# BoardA-Storage.net
KiCad netlist of a schematic drawn in Altium Designer
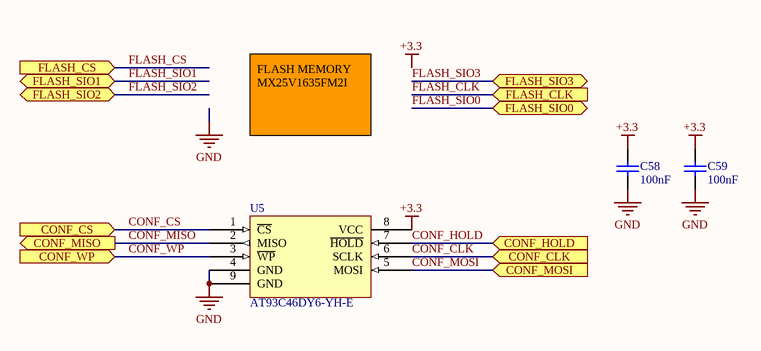
[diagram p0: BoardA-Storage.SchDoc]

(export (version "E")
  (design (tool "Eeschema 10.0.6"))
  (components
    (comp (ref "C58")
      (value "100nF")
      (footprint "CAPC0603X33X15ML03T05")
      (fields (field (name "MANUFACTURER") "Samsung") (field (name "PART NUMBER") "CL03A104KQ3NNNC"))
      (libsource (lib "Altium Content Vault") (part "CAP"))
    )
    (comp (ref "C59")
      (value "100nF")
      (footprint "CAPC0603X33X15ML03T05")
      (fields (field (name "MANUFACTURER") "Samsung") (field (name "PART NUMBER") "CL03A104KQ3NNNC"))
      (libsource (lib "Altium Content Vault") (part "CAP"))
    )
    (comp (ref "U5")
      (value "AT93C46DY6-YH-E")
      (footprint "AT93C46DY6-YH-E")
      (description "EEPROM Memory IC 1Kb (128 x 8, 64 x 16) SPI 8-UDFN (2x3)")
      (fields
        (field (name "MANUFACTURER") "Microchip")
        (field (name "MANUFACTURER PART NUMBER") "AT25040B-MAHL-E")
      )
      (libsource (lib "BoardA") (part "AT93C46DY6-YH-E"))
    )
  )
  (nets
    (net (code "1") (name "+3.3") (class "Default")
      (node (ref "C58") (pin "2") (pinfunction "2_2") (pintype "passive"))
      (node (ref "C59") (pin "2") (pinfunction "2_2") (pintype "passive"))
      (node (ref "U5") (pin "8") (pinfunction "VCC_8") (pintype "power_in"))
    )
    (net (code "2") (name "/CONF_CLK") (class "Default")
      (node (ref "U5") (pin "6") (pinfunction "SCLK_6") (pintype "input"))
    )
    (net (code "3") (name "/CONF_CS") (class "Default")
      (node (ref "U5") (pin "1") (pinfunction "~{CS}_1") (pintype "input"))
    )
    (net (code "4") (name "/CONF_HOLD") (class "Default")
      (node (ref "U5") (pin "7") (pinfunction "~{HOLD}_7") (pintype "input"))
    )
    (net (code "5") (name "/CONF_MISO") (class "Default")
      (node (ref "U5") (pin "2") (pinfunction "MISO_2") (pintype "output"))
    )
    (net (code "6") (name "/CONF_MOSI") (class "Default")
      (node (ref "U5") (pin "5") (pinfunction "MOSI_5") (pintype "input"))
    )
    (net (code "7") (name "/CONF_WP") (class "Default")
      (node (ref "U5") (pin "3") (pinfunction "~{WP}_3") (pintype "input"))
    )
    (net (code "14") (name "GND") (class "Default")
      (node (ref "C58") (pin "1") (pinfunction "1_1") (pintype "passive"))
      (node (ref "C59") (pin "1") (pinfunction "1_1") (pintype "passive"))
      (node (ref "U5") (pin "4") (pinfunction "GND_4") (pintype "power_in"))
      (node (ref "U5") (pin "9") (pinfunction "GND_9") (pintype "power_in"))
    )
  )
)
